# HC_Standoff.net
KiCad netlist of a schematic drawn in Altium Designer
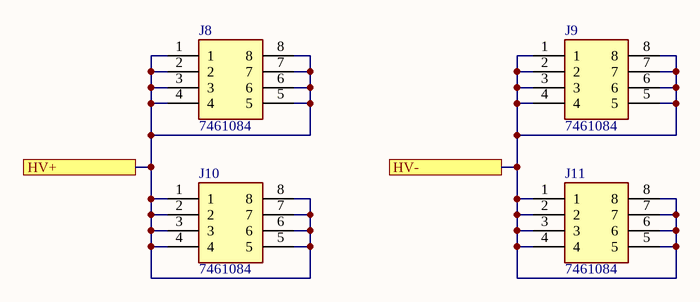
[diagram p0: HC Standoff.SchDoc]

(export (version "E")
  (design (tool "Eeschema 10.0.6"))
  (components
    (comp (ref "J8")
      (value "7461084")
      (footprint "SamacSys:7461084")
      (description "Connector")
      (fields (field (name "MOUSER PART NUMBER") "710-7461084"))
      (libsource (lib "*") (part "7461084"))
    )
    (comp (ref "J9")
      (value "7461084")
      (footprint "SamacSys:7461084")
      (description "Connector")
      (fields (field (name "MOUSER PART NUMBER") "710-7461084"))
      (libsource (lib "*") (part "7461084"))
    )
    (comp (ref "J10")
      (value "7461084")
      (footprint "SamacSys:7461084")
      (description "Connector")
      (fields (field (name "MOUSER PART NUMBER") "710-7461084"))
      (libsource (lib "*") (part "7461084"))
    )
    (comp (ref "J11")
      (value "7461084")
      (footprint "SamacSys:7461084")
      (description "Connector")
      (fields (field (name "MOUSER PART NUMBER") "710-7461084"))
      (libsource (lib "*") (part "7461084"))
    )
  )
  (nets
    (net (code "1") (name "/HV+") (class "Default")
      (node (ref "J10") (pin "1") (pinfunction "1_1") (pintype "passive"))
      (node (ref "J10") (pin "2") (pinfunction "2_2") (pintype "passive"))
      (node (ref "J10") (pin "3") (pinfunction "3_3") (pintype "passive"))
      (node (ref "J10") (pin "4") (pinfunction "4_4") (pintype "passive"))
      (node (ref "J10") (pin "5") (pinfunction "5_5") (pintype "passive"))
      (node (ref "J10") (pin "6") (pinfunction "6_6") (pintype "passive"))
      (node (ref "J10") (pin "7") (pinfunction "7_7") (pintype "passive"))
      (node (ref "J10") (pin "8") (pinfunction "8_8") (pintype "passive"))
      (node (ref "J8") (pin "1") (pinfunction "1_1") (pintype "passive"))
      (node (ref "J8") (pin "2") (pinfunction "2_2") (pintype "passive"))
      (node (ref "J8") (pin "3") (pinfunction "3_3") (pintype "passive"))
      (node (ref "J8") (pin "4") (pinfunction "4_4") (pintype "passive"))
      (node (ref "J8") (pin "5") (pinfunction "5_5") (pintype "passive"))
      (node (ref "J8") (pin "6") (pinfunction "6_6") (pintype "passive"))
      (node (ref "J8") (pin "7") (pinfunction "7_7") (pintype "passive"))
      (node (ref "J8") (pin "8") (pinfunction "8_8") (pintype "passive"))
    )
    (net (code "2") (name "/HV-") (class "Default")
      (node (ref "J11") (pin "1") (pinfunction "1_1") (pintype "passive"))
      (node (ref "J11") (pin "2") (pinfunction "2_2") (pintype "passive"))
      (node (ref "J11") (pin "3") (pinfunction "3_3") (pintype "passive"))
      (node (ref "J11") (pin "4") (pinfunction "4_4") (pintype "passive"))
      (node (ref "J11") (pin "5") (pinfunction "5_5") (pintype "passive"))
      (node (ref "J11") (pin "6") (pinfunction "6_6") (pintype "passive"))
      (node (ref "J11") (pin "7") (pinfunction "7_7") (pintype "passive"))
      (node (ref "J11") (pin "8") (pinfunction "8_8") (pintype "passive"))
      (node (ref "J9") (pin "1") (pinfunction "1_1") (pintype "passive"))
      (node (ref "J9") (pin "2") (pinfunction "2_2") (pintype "passive"))
      (node (ref "J9") (pin "3") (pinfunction "3_3") (pintype "passive"))
      (node (ref "J9") (pin "4") (pinfunction "4_4") (pintype "passive"))
      (node (ref "J9") (pin "5") (pinfunction "5_5") (pintype "passive"))
      (node (ref "J9") (pin "6") (pinfunction "6_6") (pintype "passive"))
      (node (ref "J9") (pin "7") (pinfunction "7_7") (pintype "passive"))
      (node (ref "J9") (pin "8") (pinfunction "8_8") (pintype "passive"))
    )
  )
)
